# RCMX_Rev_01.net
KiCad netlist of a schematic drawn in EAGLE
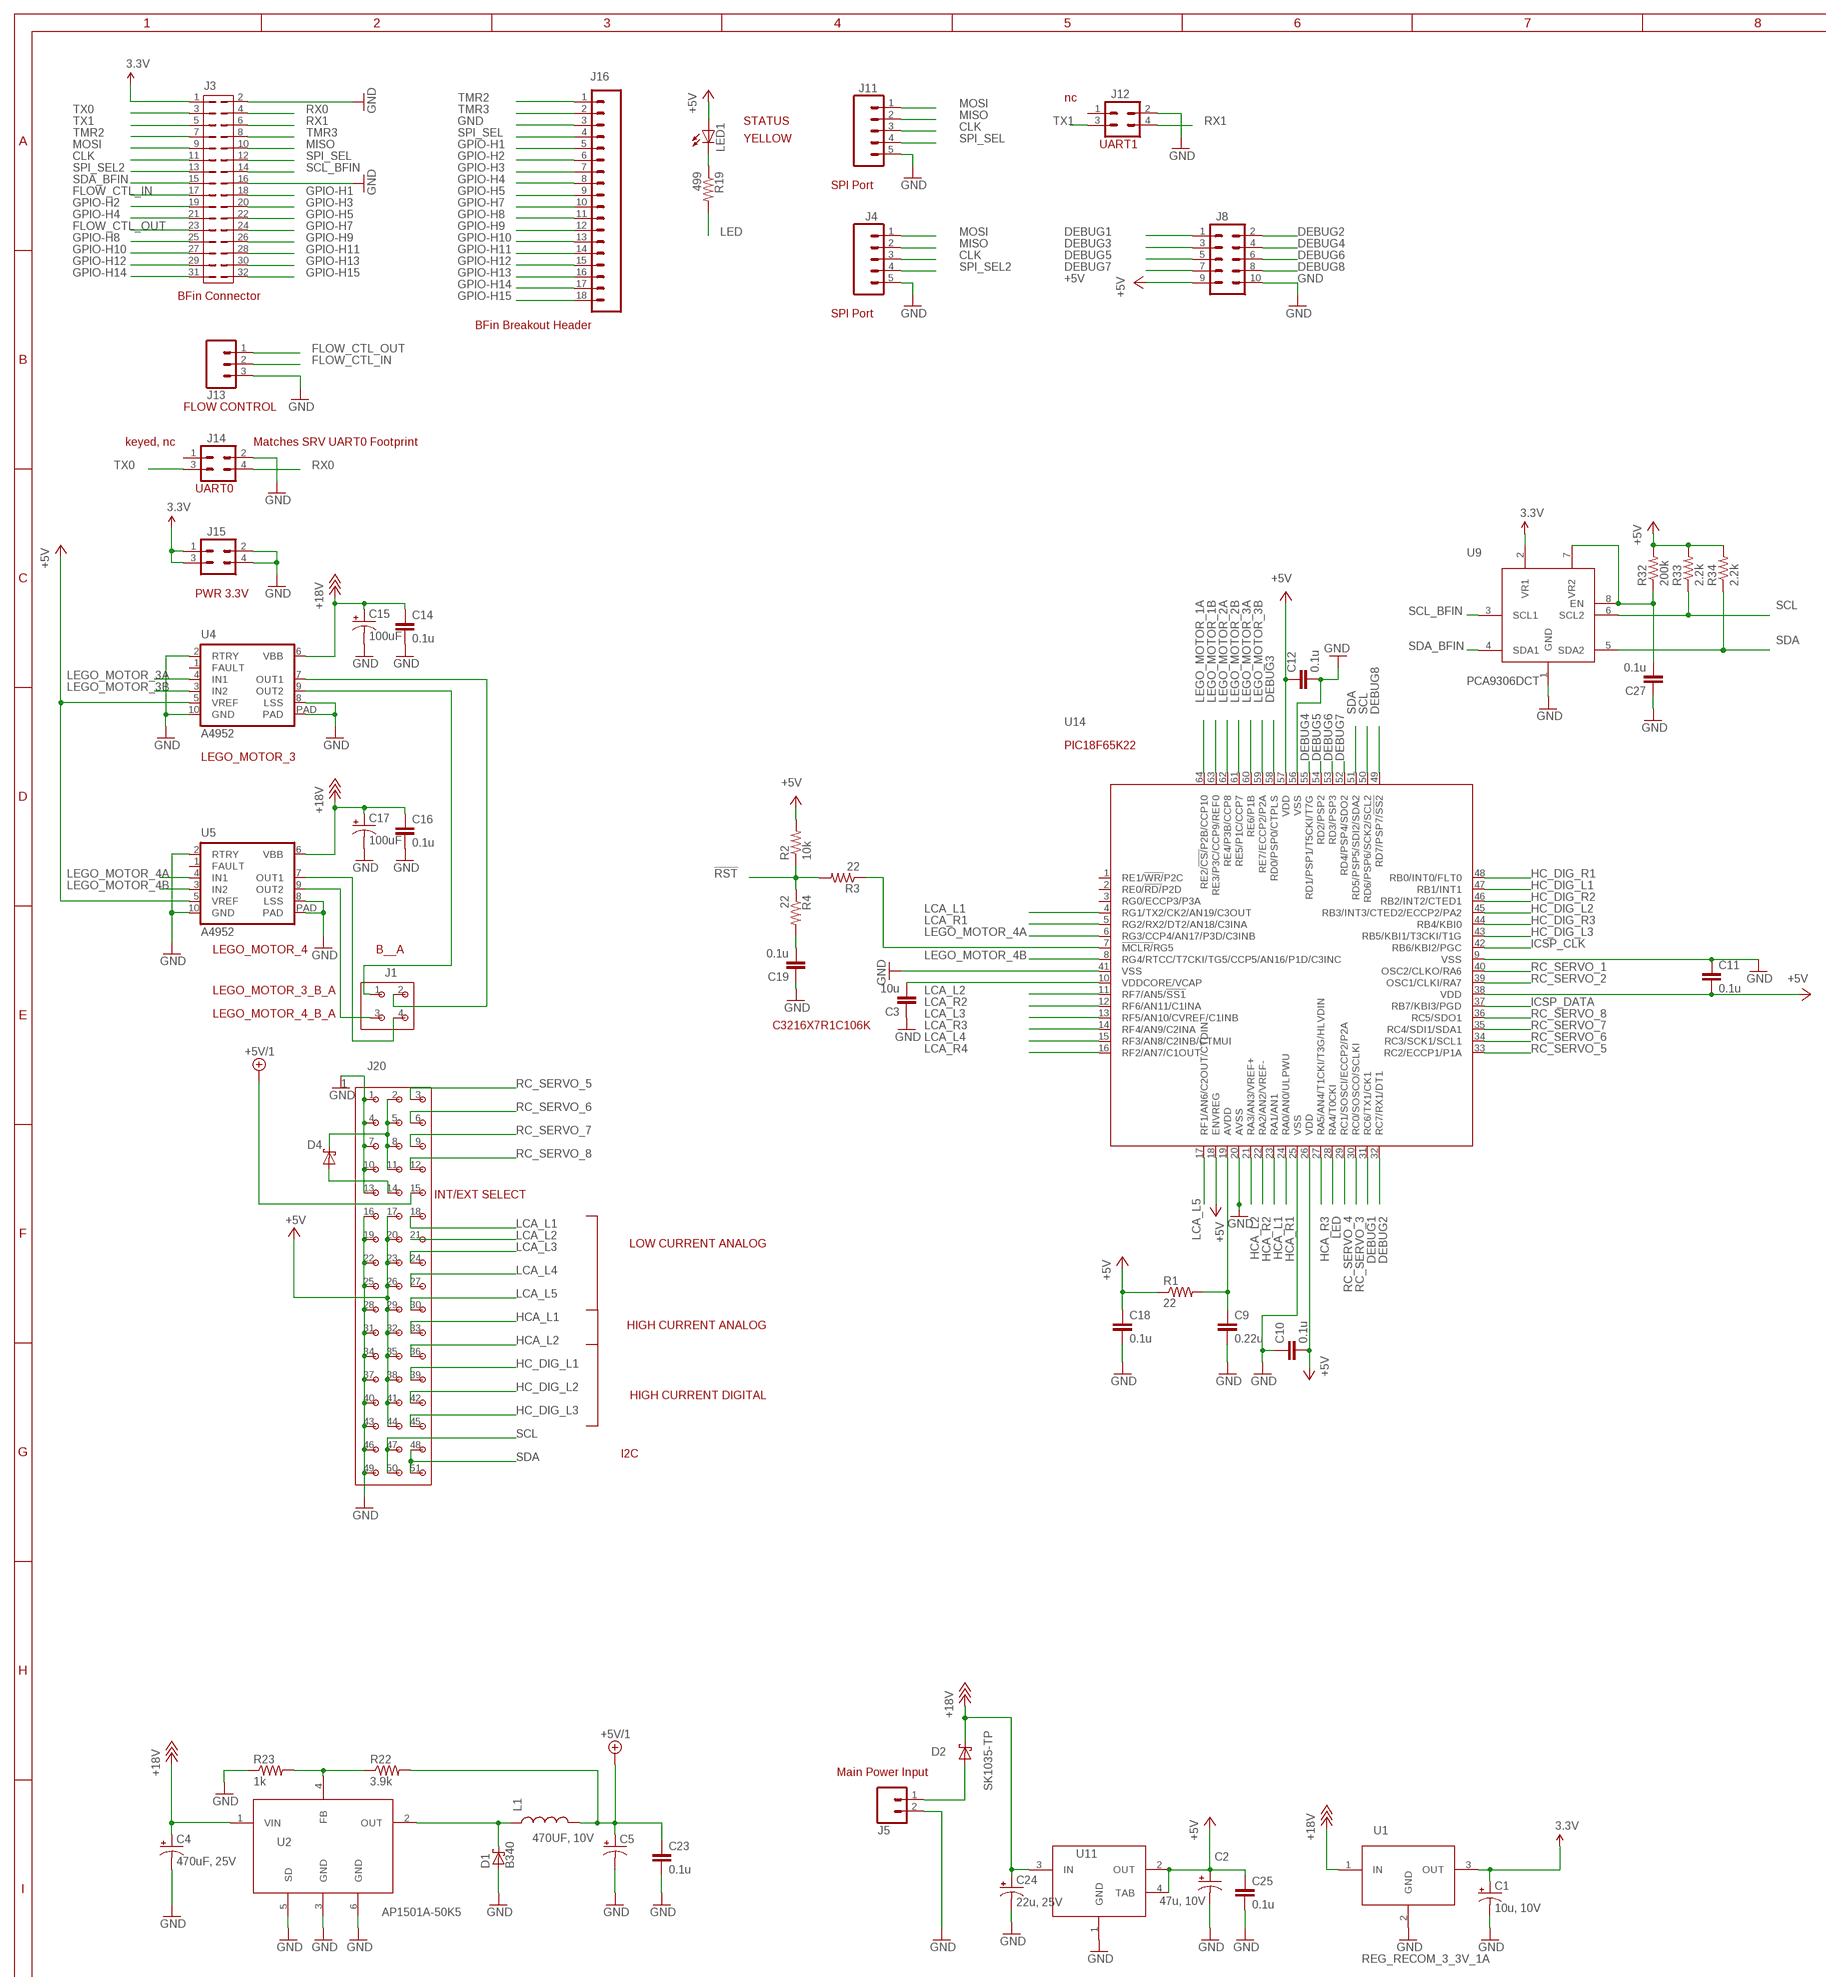
[diagram p0: schematic, sheet 1, part 1 of 2]
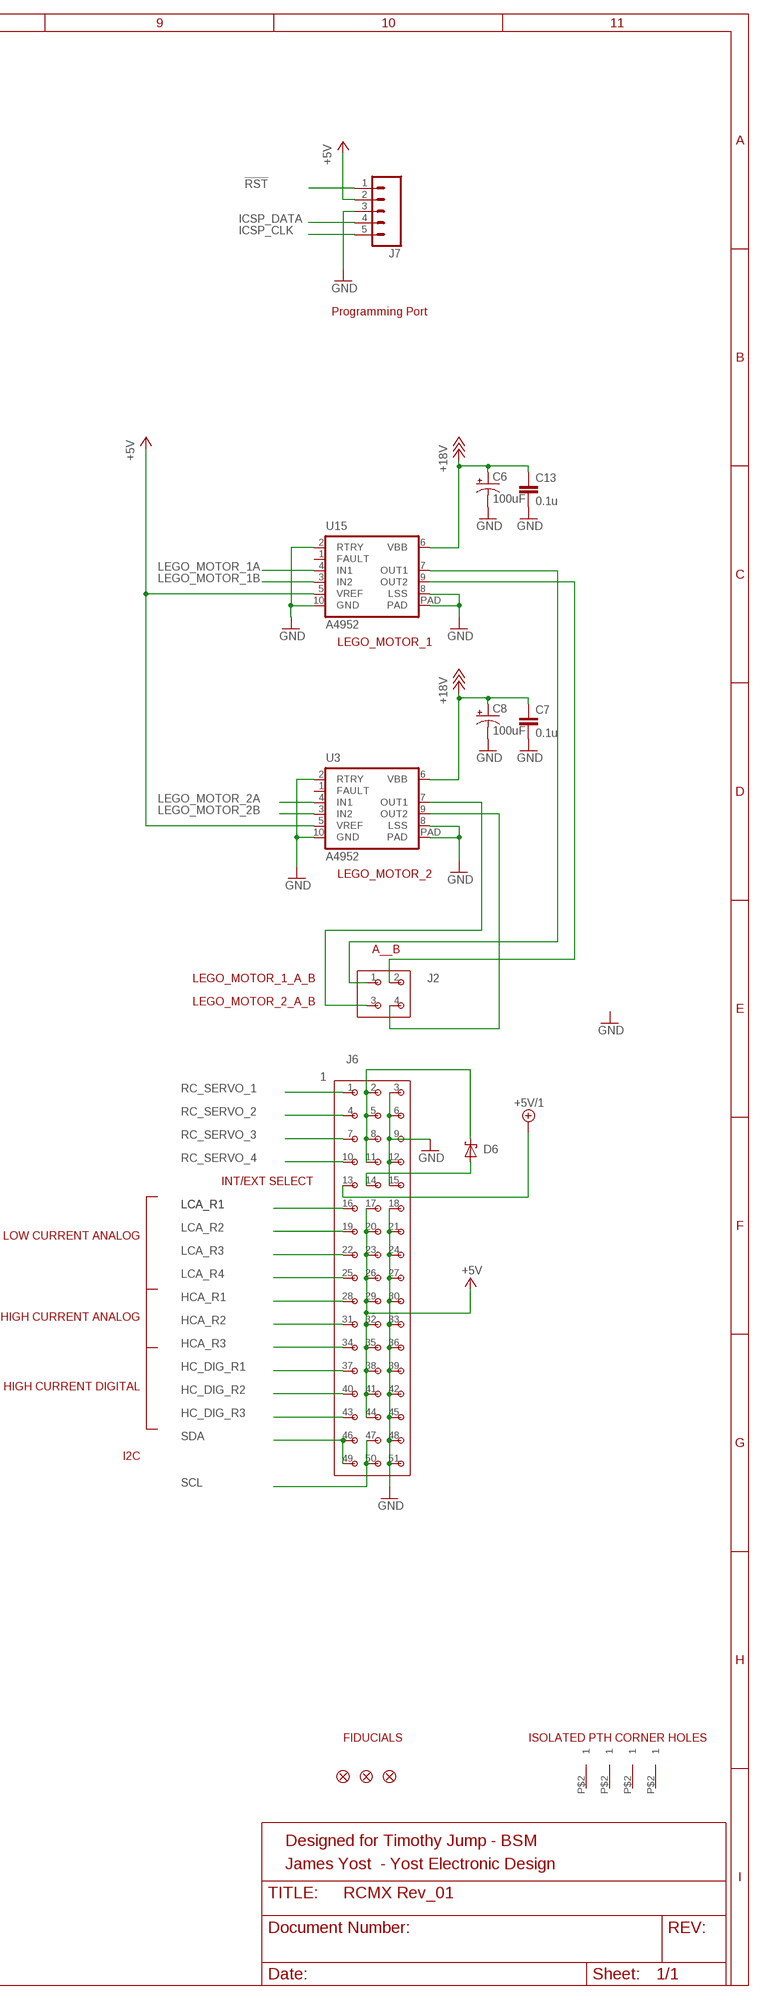
[diagram p1: schematic, sheet 1, part 2 of 2]

(export (version "E")
  (design (tool "Eeschema 10.0.6"))
  (components
    (comp (ref "C1")
      (value "10u, 10V")
      (footprint "eagle-import:EIA3216")
      (libsource (lib "eagle-import") (part "CAP_POL1206"))
    )
    (comp (ref "C2")
      (value "47u, 10V")
      (footprint "eagle-import:CAP1210_POL")
      (libsource (lib "eagle-import") (part "CAP_1210_POL"))
    )
    (comp (ref "C3")
      (value "10u")
      (footprint "eagle-import:1206")
      (libsource (lib "eagle-import") (part "CAP1206"))
    )
    (comp (ref "C4")
      (value "470uF, 25V")
      (footprint "eagle-import:PANASONIC_G")
      (libsource (lib "eagle-import") (part "CAP_POLG"))
    )
    (comp (ref "C5")
      (value "470UF, 10V")
      (footprint "eagle-import:PANASONIC_F")
      (libsource (lib "eagle-import") (part "CAP_ELT_PANASONIC_470UF"))
    )
    (comp (ref "C6")
      (value "100uF")
      (footprint "eagle-import:PANASONIC_D")
      (libsource (lib "eagle-import") (part "CAP_POLD"))
    )
    (comp (ref "C7")
      (value "0.1u")
      (footprint "eagle-import:0805")
      (libsource (lib "eagle-import") (part "CAP0805"))
    )
    (comp (ref "C8")
      (value "100uF")
      (footprint "eagle-import:PANASONIC_D")
      (libsource (lib "eagle-import") (part "CAP_POLD"))
    )
    (comp (ref "C9")
      (value "0.22u")
      (footprint "eagle-import:0805")
      (libsource (lib "eagle-import") (part "CAP0805"))
    )
    (comp (ref "C10")
      (value "0.1u")
      (footprint "eagle-import:0805")
      (libsource (lib "eagle-import") (part "CAP0805"))
    )
    (comp (ref "C11")
      (value "0.1u")
      (footprint "eagle-import:0805")
      (libsource (lib "eagle-import") (part "CAP0805"))
    )
    (comp (ref "C12")
      (value "0.1u")
      (footprint "eagle-import:0805")
      (libsource (lib "eagle-import") (part "CAP0805"))
    )
    (comp (ref "C13")
      (value "0.1u")
      (footprint "eagle-import:0805")
      (libsource (lib "eagle-import") (part "CAP0805"))
    )
    (comp (ref "C14")
      (value "0.1u")
      (footprint "eagle-import:0805")
      (libsource (lib "eagle-import") (part "CAP0805"))
    )
    (comp (ref "C15")
      (value "100uF")
      (footprint "eagle-import:PANASONIC_D")
      (libsource (lib "eagle-import") (part "CAP_POLD"))
    )
    (comp (ref "C16")
      (value "0.1u")
      (footprint "eagle-import:0805")
      (libsource (lib "eagle-import") (part "CAP0805"))
    )
    (comp (ref "C17")
      (value "100uF")
      (footprint "eagle-import:PANASONIC_D")
      (libsource (lib "eagle-import") (part "CAP_POLD"))
    )
    (comp (ref "C18")
      (value "0.1u")
      (footprint "eagle-import:0805")
      (libsource (lib "eagle-import") (part "CAP0805"))
    )
    (comp (ref "C19")
      (value "0.1u")
      (footprint "eagle-import:0805")
      (libsource (lib "eagle-import") (part "CAP0805"))
    )
    (comp (ref "C23")
      (value "0.1u")
      (footprint "eagle-import:0805")
      (libsource (lib "eagle-import") (part "CAP0805"))
    )
    (comp (ref "C24")
      (value "22u, 25V")
      (footprint "eagle-import:CAP1210_POL")
      (libsource (lib "eagle-import") (part "CAP_1210_POL"))
    )
    (comp (ref "C25")
      (value "0.1u")
      (footprint "eagle-import:0805")
      (libsource (lib "eagle-import") (part "CAP0805"))
    )
    (comp (ref "C27")
      (value "0.1u")
      (footprint "eagle-import:0805")
      (libsource (lib "eagle-import") (part "CAP0805"))
    )
    (comp (ref "D1")
      (value "B340")
      (footprint "eagle-import:SMA_DO214AC")
      (libsource (lib "eagle-import") (part "B340"))
    )
    (comp (ref "D2")
      (value "SK1035-TP")
      (footprint "eagle-import:DO214AB")
      (libsource (lib "eagle-import") (part "SK1035-TP"))
    )
    (comp (ref "D4")
      (value "SK1035-TP")
      (footprint "eagle-import:DO214AB")
      (libsource (lib "eagle-import") (part "SK1035-TP"))
    )
    (comp (ref "D6")
      (value "SK1035-TP")
      (footprint "eagle-import:DO214AB")
      (libsource (lib "eagle-import") (part "SK1035-TP"))
    )
    (comp (ref "J1")
      (value "CON_2X2_0_100")
      (footprint "eagle-import:CON_2X2_0_100")
      (libsource (lib "eagle-import") (part "CON_2X2_0_100"))
    )
    (comp (ref "J2")
      (value "CON_2X2_0_100")
      (footprint "eagle-import:CON_2X2_0_100")
      (libsource (lib "eagle-import") (part "CON_2X2_0_100"))
    )
    (comp (ref "J3")
      (value "CON_2X16_0_100")
      (footprint "eagle-import:CON_2X16_0_100")
      (libsource (lib "eagle-import") (part "CON_2X16_0_100"))
    )
    (comp (ref "J4")
      (value "M05PTH")
      (footprint "eagle-import:1X05")
      (libsource (lib "eagle-import") (part "M05PTH"))
    )
    (comp (ref "J5")
      (value "M02NG")
      (footprint "eagle-import:1X02")
      (libsource (lib "eagle-import") (part "M02NG"))
    )
    (comp (ref "J6")
      (value "CON_3X17_0_100")
      (footprint "eagle-import:CON_3X17_0_100")
      (libsource (lib "eagle-import") (part "CON_3X17_0_100"))
    )
    (comp (ref "J7")
      (value "M05PTH")
      (footprint "eagle-import:1X05")
      (libsource (lib "eagle-import") (part "SparkFun-Connectors_M05PTH"))
    )
    (comp (ref "J8")
      (value "M05X2PTH")
      (footprint "eagle-import:AVR_ICSP")
      (libsource (lib "eagle-import") (part "M05X2PTH"))
    )
    (comp (ref "J11")
      (value "M05PTH")
      (footprint "eagle-import:1X05")
      (libsource (lib "eagle-import") (part "M05PTH"))
    )
    (comp (ref "J12")
      (value "CON2X2")
      (footprint "eagle-import:CON2X2")
      (libsource (lib "eagle-import") (part "CON2X2"))
    )
    (comp (ref "J13")
      (value "M03PTH")
      (footprint "eagle-import:1X03")
      (libsource (lib "eagle-import") (part "M03PTH"))
    )
    (comp (ref "J14")
      (value "CON2X2")
      (footprint "eagle-import:CON2X2")
      (libsource (lib "eagle-import") (part "CON2X2"))
    )
    (comp (ref "J15")
      (value "CON2X2")
      (footprint "eagle-import:CON2X2")
      (libsource (lib "eagle-import") (part "CON2X2"))
    )
    (comp (ref "J16")
      (value "CON1X18")
      (footprint "eagle-import:CON1X18")
      (libsource (lib "eagle-import") (part "CON1X18"))
    )
    (comp (ref "J20")
      (value "CON_3X17_0_100")
      (footprint "eagle-import:CON_3X17_0_100")
      (libsource (lib "eagle-import") (part "CON_3X17_0_100"))
    )
    (comp (ref "L1")
      (value "IND_47UH_COILTRONICS_2_95A")
      (footprint "eagle-import:IND_PADS_SMT")
      (libsource (lib "eagle-import") (part "IND_47UH_COILTRONICS_2_95A"))
    )
    (comp (ref "LED1")
      (value "LEDCHIP-LED0805")
      (footprint "eagle-import:CHIP-LED0805")
      (libsource (lib "eagle-import") (part "LEDCHIP-LED0805"))
    )
    (comp (ref "R1")
      (value "22")
      (footprint "eagle-import:0805")
      (libsource (lib "eagle-import") (part "RESISTOR"))
    )
    (comp (ref "R2")
      (value "10k")
      (footprint "eagle-import:0805")
      (libsource (lib "eagle-import") (part "RESISTOR"))
    )
    (comp (ref "R3")
      (value "22")
      (footprint "eagle-import:0805")
      (libsource (lib "eagle-import") (part "RESISTOR"))
    )
    (comp (ref "R4")
      (value "22")
      (footprint "eagle-import:0805")
      (libsource (lib "eagle-import") (part "RESISTOR"))
    )
    (comp (ref "R19")
      (value "499")
      (footprint "eagle-import:0805")
      (libsource (lib "eagle-import") (part "RESISTOR"))
    )
    (comp (ref "R22")
      (value "3.9k")
      (footprint "eagle-import:0805")
      (libsource (lib "eagle-import") (part "RESISTOR"))
    )
    (comp (ref "R23")
      (value "1k")
      (footprint "eagle-import:0805")
      (libsource (lib "eagle-import") (part "RESISTOR"))
    )
    (comp (ref "R32")
      (value "200k")
      (footprint "eagle-import:0805")
      (libsource (lib "eagle-import") (part "RESISTOR"))
    )
    (comp (ref "R33")
      (value "2.2k")
      (footprint "eagle-import:0805")
      (libsource (lib "eagle-import") (part "RESISTOR"))
    )
    (comp (ref "R34")
      (value "2.2k")
      (footprint "eagle-import:0805")
      (libsource (lib "eagle-import") (part "RESISTOR"))
    )
    (comp (ref "U$1")
      (value "GNDPAD")
      (footprint "eagle-import:GNDPAD")
      (libsource (lib "eagle-import") (part "GNDPAD"))
    )
    (comp (ref "U$2")
      (value "GNDPAD")
      (footprint "eagle-import:GNDPAD")
      (libsource (lib "eagle-import") (part "GNDPAD"))
    )
    (comp (ref "U$3")
      (value "FIDUCIAL1X2.5")
      (footprint "eagle-import:FIDUCIAL-1X2.5")
      (libsource (lib "eagle-import") (part "FIDUCIAL1X2.5"))
    )
    (comp (ref "U$4")
      (value "FIDUCIAL1X2.5")
      (footprint "eagle-import:FIDUCIAL-1X2.5")
      (libsource (lib "eagle-import") (part "FIDUCIAL1X2.5"))
    )
    (comp (ref "U$5")
      (value "FIDUCIAL1X2.5")
      (footprint "eagle-import:FIDUCIAL-1X2.5")
      (libsource (lib "eagle-import") (part "FIDUCIAL1X2.5"))
    )
    (comp (ref "U$7")
      (value "GNDPAD")
      (footprint "eagle-import:GNDPAD")
      (libsource (lib "eagle-import") (part "GNDPAD"))
    )
    (comp (ref "U$8")
      (value "GNDPAD")
      (footprint "eagle-import:GNDPAD")
      (libsource (lib "eagle-import") (part "GNDPAD"))
    )
    (comp (ref "U1")
      (value "REG_RECOM_3_3V_1A")
      (footprint "eagle-import:REG_RECOM_3_3V_1A")
      (libsource (lib "eagle-import") (part "REG_RECOM_3_3V_1A"))
    )
    (comp (ref "U2")
      (value "AP1501A-50K5")
      (footprint "eagle-import:TO263-5")
      (libsource (lib "eagle-import") (part "AP1501A-50K5"))
    )
    (comp (ref "U3")
      (value "A4952")
      (footprint "eagle-import:MSOP10_W_THERMAL_PAD")
      (libsource (lib "eagle-import") (part "A4952"))
    )
    (comp (ref "U4")
      (value "A4952")
      (footprint "eagle-import:MSOP10_W_THERMAL_PAD")
      (libsource (lib "eagle-import") (part "A4952"))
    )
    (comp (ref "U5")
      (value "A4952")
      (footprint "eagle-import:MSOP10_W_THERMAL_PAD")
      (libsource (lib "eagle-import") (part "A4952"))
    )
    (comp (ref "U9")
      (value "PCA9306DCT")
      (footprint "eagle-import:TEST08")
      (libsource (lib "eagle-import") (part "PCA9306DCT"))
    )
    (comp (ref "U11")
      (value "TLV1117-5")
      (footprint "eagle-import:SOT223")
      (libsource (lib "eagle-import") (part "TLV1117-5"))
    )
    (comp (ref "U14")
      (value "MICRO_C_PIC18F65K22")
      (footprint "eagle-import:64PIN_TQFP_10X10X1MM")
      (libsource (lib "eagle-import") (part "MICRO_C_PIC18F65K22"))
    )
    (comp (ref "U15")
      (value "A4952")
      (footprint "eagle-import:MSOP10_W_THERMAL_PAD")
      (libsource (lib "eagle-import") (part "A4952"))
    )
  )
  (nets
    (net (code "1") (name "+5V") (class "Default")
      (node (ref "C10") (pin "2") (pinfunction "2_2") (pintype "passive"))
      (node (ref "C11") (pin "2") (pinfunction "2_2") (pintype "passive"))
      (node (ref "C12") (pin "1") (pinfunction "1_1") (pintype "passive"))
      (node (ref "C18") (pin "1") (pinfunction "1_1") (pintype "passive"))
      (node (ref "C2") (pin "1") (pinfunction "+_1") (pintype "passive"))
      (node (ref "C25") (pin "1") (pinfunction "1_1") (pintype "passive"))
      (node (ref "J20") (pin "17") (pinfunction "17_17") (pintype "passive"))
      (node (ref "J20") (pin "20") (pinfunction "20_20") (pintype "passive"))
      (node (ref "J20") (pin "23") (pinfunction "23_23") (pintype "passive"))
      (node (ref "J20") (pin "26") (pinfunction "26_26") (pintype "passive"))
      (node (ref "J20") (pin "29") (pinfunction "29_29") (pintype "passive"))
      (node (ref "J20") (pin "32") (pinfunction "32_32") (pintype "passive"))
      (node (ref "J20") (pin "35") (pinfunction "35_35") (pintype "passive"))
      (node (ref "J20") (pin "38") (pinfunction "38_38") (pintype "passive"))
      (node (ref "J20") (pin "41") (pinfunction "41_41") (pintype "passive"))
      (node (ref "J20") (pin "44") (pinfunction "44_44") (pintype "passive"))
      (node (ref "J6") (pin "17") (pinfunction "17_17") (pintype "passive"))
      (node (ref "J6") (pin "20") (pinfunction "20_20") (pintype "passive"))
      (node (ref "J6") (pin "23") (pinfunction "23_23") (pintype "passive"))
      (node (ref "J6") (pin "26") (pinfunction "26_26") (pintype "passive"))
      (node (ref "J6") (pin "29") (pinfunction "29_29") (pintype "passive"))
      (node (ref "J6") (pin "32") (pinfunction "32_32") (pintype "passive"))
      (node (ref "J6") (pin "35") (pinfunction "35_35") (pintype "passive"))
      (node (ref "J6") (pin "38") (pinfunction "38_38") (pintype "passive"))
      (node (ref "J6") (pin "41") (pinfunction "41_41") (pintype "passive"))
      (node (ref "J6") (pin "44") (pinfunction "44_44") (pintype "passive"))
      (node (ref "J7") (pin "2") (pinfunction "2_2") (pintype "passive"))
      (node (ref "J8") (pin "9") (pinfunction "9_9") (pintype "passive"))
      (node (ref "LED1") (pin "A") (pinfunction "A_A") (pintype "passive"))
      (node (ref "R1") (pin "1") (pinfunction "1_1") (pintype "passive"))
      (node (ref "R2") (pin "2") (pinfunction "2_2") (pintype "passive"))
      (node (ref "R32") (pin "2") (pinfunction "2_2") (pintype "passive"))
      (node (ref "R33") (pin "2") (pinfunction "2_2") (pintype "passive"))
      (node (ref "R34") (pin "2") (pinfunction "2_2") (pintype "passive"))
      (node (ref "U11") (pin "2") (pinfunction "OUT_2") (pintype "bidirectional"))
      (node (ref "U11") (pin "4") (pinfunction "TAB_4") (pintype "bidirectional"))
      (node (ref "U14") (pin "18") (pinfunction "ENVREG_18") (pintype "input"))
      (node (ref "U14") (pin "26") (pinfunction "VDD_26") (pintype "power_in"))
      (node (ref "U14") (pin "38") (pinfunction "VDD_38") (pintype "power_in"))
      (node (ref "U14") (pin "57") (pinfunction "VDD_57") (pintype "power_in"))
      (node (ref "U15") (pin "5") (pinfunction "VREF_5") (pintype "passive"))
      (node (ref "U3") (pin "5") (pinfunction "VREF_5") (pintype "passive"))
      (node (ref "U4") (pin "5") (pinfunction "VREF_5") (pintype "passive"))
      (node (ref "U5") (pin "5") (pinfunction "VREF_5") (pintype "passive"))
    )
    (net (code "2") (name "+5V{slash}1") (class "Default")
      (node (ref "C23") (pin "1") (pinfunction "1_1") (pintype "passive"))
      (node (ref "C5") (pin "+") (pinfunction "+_+") (pintype "passive"))
      (node (ref "J20") (pin "15") (pinfunction "15_15") (pintype "passive"))
      (node (ref "J6") (pin "13") (pinfunction "13_13") (pintype "passive"))
      (node (ref "L1") (pin "2") (pinfunction "2_2") (pintype "passive"))
      (node (ref "R22") (pin "2") (pinfunction "2_2") (pintype "passive"))
    )
    (net (code "3") (name "+18V") (class "Default")
      (node (ref "C13") (pin "1") (pinfunction "1_1") (pintype "passive"))
      (node (ref "C14") (pin "1") (pinfunction "1_1") (pintype "passive"))
      (node (ref "C15") (pin "+") (pinfunction "+_+") (pintype "passive"))
      (node (ref "C16") (pin "1") (pinfunction "1_1") (pintype "passive"))
      (node (ref "C17") (pin "+") (pinfunction "+_+") (pintype "passive"))
      (node (ref "C24") (pin "1") (pinfunction "+_1") (pintype "passive"))
      (node (ref "C4") (pin "+") (pinfunction "+_+") (pintype "passive"))
      (node (ref "C6") (pin "+") (pinfunction "+_+") (pintype "passive"))
      (node (ref "C7") (pin "1") (pinfunction "1_1") (pintype "passive"))
      (node (ref "C8") (pin "+") (pinfunction "+_+") (pintype "passive"))
      (node (ref "D2") (pin "1") (pinfunction "C_1") (pintype "passive"))
      (node (ref "U1") (pin "1") (pinfunction "IN_1") (pintype "bidirectional"))
      (node (ref "U11") (pin "3") (pinfunction "IN_3") (pintype "bidirectional"))
      (node (ref "U15") (pin "6") (pinfunction "VBB_6") (pintype "input"))
      (node (ref "U2") (pin "1") (pinfunction "VIN_1") (pintype "bidirectional"))
      (node (ref "U3") (pin "6") (pinfunction "VBB_6") (pintype "input"))
      (node (ref "U4") (pin "6") (pinfunction "VBB_6") (pintype "input"))
      (node (ref "U5") (pin "6") (pinfunction "VBB_6") (pintype "input"))
    )
    (net (code "4") (name "/CLK") (class "Default")
      (node (ref "J11") (pin "3") (pinfunction "3_3") (pintype "passive"))
      (node (ref "J3") (pin "11") (pinfunction "11_11") (pintype "passive"))
      (node (ref "J4") (pin "3") (pinfunction "3_3") (pintype "passive"))
    )
    (net (code "5") (name "/DEBUG1") (class "Default")
      (node (ref "J8") (pin "1") (pinfunction "1_1") (pintype "passive"))
      (node (ref "U14") (pin "31") (pinfunction "RC6/TX1/CK1_31") (pintype "bidirectional"))
    )
    (net (code "6") (name "/DEBUG2") (class "Default")
      (node (ref "J8") (pin "2") (pinfunction "2_2") (pintype "passive"))
      (node (ref "U14") (pin "32") (pinfunction "RC7/RX1/DT1_32") (pintype "bidirectional"))
    )
    (net (code "7") (name "/DEBUG3") (class "Default")
      (node (ref "J8") (pin "3") (pinfunction "3_3") (pintype "passive"))
      (node (ref "U14") (pin "58") (pinfunction "RD0/PSP0/CTPLS_58") (pintype "bidirectional"))
    )
    (net (code "8") (name "/DEBUG4") (class "Default")
      (node (ref "J8") (pin "4") (pinfunction "4_4") (pintype "passive"))
      (node (ref "U14") (pin "55") (pinfunction "RD1/PSP1/T5CKI/T7G_55") (pintype "bidirectional"))
    )
    (net (code "9") (name "/DEBUG5") (class "Default")
      (node (ref "J8") (pin "5") (pinfunction "5_5") (pintype "passive"))
      (node (ref "U14") (pin "54") (pinfunction "RD2/PSP2_54") (pintype "bidirectional"))
    )
    (net (code "10") (name "/DEBUG6") (class "Default")
      (node (ref "J8") (pin "6") (pinfunction "6_6") (pintype "passive"))
      (node (ref "U14") (pin "53") (pinfunction "RD3/PSP3_53") (pintype "bidirectional"))
    )
    (net (code "11") (name "/DEBUG7") (class "Default")
      (node (ref "J8") (pin "7") (pinfunction "7_7") (pintype "passive"))
      (node (ref "U14") (pin "52") (pinfunction "RD4/PSP4/SDO2_52") (pintype "bidirectional"))
    )
    (net (code "12") (name "/DEBUG8") (class "Default")
      (node (ref "J8") (pin "8") (pinfunction "8_8") (pintype "passive"))
      (node (ref "U14") (pin "49") (pinfunction "RD7/PSP7/~{SS2}_49") (pintype "bidirectional"))
    )
    (net (code "13") (name "/FLOW_CTL_IN") (class "Default")
      (node (ref "J13") (pin "2") (pinfunction "2_2") (pintype "passive"))
      (node (ref "J3") (pin "17") (pinfunction "17_17") (pintype "passive"))
    )
    (net (code "14") (name "/FLOW_CTL_OUT") (class "Default")
      (node (ref "J13") (pin "1") (pinfunction "1_1") (pintype "passive"))
      (node (ref "J3") (pin "23") (pinfunction "23_23") (pintype "passive"))
    )
    (net (code "15") (name "/GPIO-H1") (class "Default")
      (node (ref "J16") (pin "5") (pinfunction "5_5") (pintype "passive"))
      (node (ref "J3") (pin "18") (pinfunction "18_18") (pintype "passive"))
    )
    (net (code "16") (name "/GPIO-H2") (class "Default")
      (node (ref "J16") (pin "6") (pinfunction "6_6") (pintype "passive"))
      (node (ref "J3") (pin "19") (pinfunction "19_19") (pintype "passive"))
    )
    (net (code "17") (name "/GPIO-H3") (class "Default")
      (node (ref "J16") (pin "7") (pinfunction "7_7") (pintype "passive"))
      (node (ref "J3") (pin "20") (pinfunction "20_20") (pintype "passive"))
    )
    (net (code "18") (name "/GPIO-H4") (class "Default")
      (node (ref "J16") (pin "8") (pinfunction "8_8") (pintype "passive"))
      (node (ref "J3") (pin "21") (pinfunction "21_21") (pintype "passive"))
    )
    (net (code "19") (name "/GPIO-H5") (class "Default")
      (node (ref "J16") (pin "9") (pinfunction "9_9") (pintype "passive"))
      (node (ref "J3") (pin "22") (pinfunction "22_22") (pintype "passive"))
    )
    (net (code "20") (name "/GPIO-H7") (class "Default")
      (node (ref "J16") (pin "10") (pinfunction "10_10") (pintype "passive"))
      (node (ref "J3") (pin "24") (pinfunction "24_24") (pintype "passive"))
    )
    (net (code "21") (name "/GPIO-H8") (class "Default")
      (node (ref "J16") (pin "11") (pinfunction "11_11") (pintype "passive"))
      (node (ref "J3") (pin "25") (pinfunction "25_25") (pintype "passive"))
    )
    (net (code "22") (name "/GPIO-H9") (class "Default")
      (node (ref "J16") (pin "12") (pinfunction "12_12") (pintype "passive"))
      (node (ref "J3") (pin "26") (pinfunction "26_26") (pintype "passive"))
    )
    (net (code "23") (name "/GPIO-H10") (class "Default")
      (node (ref "J16") (pin "13") (pinfunction "13_13") (pintype "passive"))
      (node (ref "J3") (pin "27") (pinfunction "27_27") (pintype "passive"))
    )
    (net (code "24") (name "/GPIO-H11") (class "Default")
      (node (ref "J16") (pin "14") (pinfunction "14_14") (pintype "passive"))
      (node (ref "J3") (pin "28") (pinfunction "28_28") (pintype "passive"))
    )
    (net (code "25") (name "/GPIO-H12") (class "Default")
      (node (ref "J16") (pin "15") (pinfunction "15_15") (pintype "passive"))
      (node (ref "J3") (pin "29") (pinfunction "29_29") (pintype "passive"))
    )
    (net (code "26") (name "/GPIO-H13") (class "Default")
      (node (ref "J16") (pin "16") (pinfunction "16_16") (pintype "passive"))
      (node (ref "J3") (pin "30") (pinfunction "30_30") (pintype "passive"))
    )
    (net (code "27") (name "/GPIO-H14") (class "Default")
      (node (ref "J16") (pin "17") (pinfunction "17_17") (pintype "passive"))
      (node (ref "J3") (pin "31") (pinfunction "31_31") (pintype "passive"))
    )
    (net (code "28") (name "/GPIO-H15") (class "Default")
      (node (ref "J16") (pin "18") (pinfunction "18_18") (pintype "passive"))
      (node (ref "J3") (pin "32") (pinfunction "32_32") (pintype "passive"))
    )
    (net (code "29") (name "/HCA_L1") (class "Default")
      (node (ref "J20") (pin "33") (pinfunction "33_33") (pintype "passive"))
      (node (ref "U14") (pin "23") (pinfunction "RA1/AN1_23") (pintype "bidirectional"))
    )
    (net (code "30") (name "/HCA_L2") (class "Default")
      (node (ref "J20") (pin "36") (pinfunction "36_36") (pintype "passive"))
      (node (ref "U14") (pin "21") (pinfunction "RA3/AN3/VREF+_21") (pintype "bidirectional"))
    )
    (net (code "31") (name "/HCA_R1") (class "Default")
      (node (ref "J6") (pin "28") (pinfunction "28_28") (pintype "passive"))
      (node (ref "U14") (pin "24") (pinfunction "RA0/AN0/ULPWU_24") (pintype "bidirectional"))
    )
    (net (code "32") (name "/HCA_R2") (class "Default")
      (node (ref "J6") (pin "31") (pinfunction "31_31") (pintype "passive"))
      (node (ref "U14") (pin "22") (pinfunction "RA2/AN2/VREF-_22") (pintype "bidirectional"))
    )
    (net (code "33") (name "/HCA_R3") (class "Default")
      (node (ref "J6") (pin "34") (pinfunction "34_34") (pintype "passive"))
      (node (ref "U14") (pin "27") (pinfunction "RA5/AN4/T1CKI/T3G/HLVDIN_27") (pintype "bidirectional"))
    )
    (net (code "34") (name "/HC_DIG_L1") (class "Default")
      (node (ref "J20") (pin "39") (pinfunction "39_39") (pintype "passive"))
      (node (ref "U14") (pin "47") (pinfunction "RB1/INT1_47") (pintype "bidirectional"))
    )
    (net (code "35") (name "/HC_DIG_L2") (class "Default")
      (node (ref "J20") (pin "42") (pinfunction "42_42") (pintype "passive"))
      (node (ref "U14") (pin "45") (pinfunction "RB3/INT3/CTED2/ECCP2/PA2_45") (pintype "bidirectional"))
    )
    (net (code "36") (name "/HC_DIG_L3") (class "Default")
      (node (ref "J20") (pin "45") (pinfunction "45_45") (pintype "passive"))
      (node (ref "U14") (pin "43") (pinfunction "RB5/KBI1/T3CKI/T1G_43") (pintype "bidirectional"))
    )
    (net (code "37") (name "/HC_DIG_R1") (class "Default")
      (node (ref "J6") (pin "37") (pinfunction "37_37") (pintype "passive"))
      (node (ref "U14") (pin "48") (pinfunction "RB0/INT0/FLT0_48") (pintype "bidirectional"))
    )
    (net (code "38") (name "/HC_DIG_R2") (class "Default")
      (node (ref "J6") (pin "40") (pinfunction "40_40") (pintype "passive"))
      (node (ref "U14") (pin "46") (pinfunction "RB2/INT2/CTED1_46") (pintype "bidirectional"))
    )
    (net (code "39") (name "/HC_DIG_R3") (class "Default")
      (node (ref "J6") (pin "43") (pinfunction "43_43") (pintype "passive"))
      (node (ref "U14") (pin "44") (pinfunction "RB4/KBI0_44") (pintype "bidirectional"))
    )
    (net (code "40") (name "/ICSP_CLK") (class "Default")
      (node (ref "J7") (pin "5") (pinfunction "5_5") (pintype "passive"))
      (node (ref "U14") (pin "42") (pinfunction "RB6/KBI2/PGC_42") (pintype "bidirectional"))
    )
    (net (code "41") (name "/ICSP_DATA") (class "Default")
      (node (ref "J7") (pin "4") (pinfunction "4_4") (pintype "passive"))
      (node (ref "U14") (pin "37") (pinfunction "RB7/KBI3/PGD_37") (pintype "bidirectional"))
    )
    (net (code "42") (name "/LCA_L1") (class "Default")
      (node (ref "J20") (pin "18") (pinfunction "18_18") (pintype "passive"))
      (node (ref "U14") (pin "4") (pinfunction "RG1/TX2/CK2/AN19/C3OUT_4") (pintype "bidirectional"))
    )
    (net (code "43") (name "/LCA_L2") (class "Default")
      (node (ref "J20") (pin "21") (pinfunction "21_21") (pintype "passive"))
      (node (ref "U14") (pin "11") (pinfunction "RF7/AN5/~{SS1}_11") (pintype "bidirectional"))
    )
    (net (code "44") (name "/LCA_L3") (class "Default")
      (node (ref "J20") (pin "24") (pinfunction "24_24") (pintype "passive"))
      (node (ref "U14") (pin "13") (pinfunction "RF5/AN10/CVREF/C1INB_13") (pintype "bidirectional"))
    )
    (net (code "45") (name "/LCA_L4") (class "Default")
      (node (ref "J20") (pin "27") (pinfunction "27_27") (pintype "passive"))
      (node (ref "U14") (pin "15") (pinfunction "RF3/AN8/C2INB/CTMUI_15") (pintype "bidirectional"))
    )
    (net (code "46") (name "/LCA_L5") (class "Default")
      (node (ref "J20") (pin "30") (pinfunction "30_30") (pintype "passive"))
      (node (ref "U14") (pin "17") (pinfunction "RF1/AN6/C2OUT/CTDIN_17") (pintype "bidirectional"))
    )
    (net (code "47") (name "/LCA_R1") (class "Default")
      (node (ref "J6") (pin "16") (pinfunction "16_16") (pintype "passive"))
      (node (ref "U14") (pin "5") (pinfunction "RG2/RX2/DT2/AN18/C3INA_5") (pintype "bidirectional"))
    )
    (net (code "48") (name "/LCA_R2") (class "Default")
      (node (ref "J6") (pin "19") (pinfunction "19_19") (pintype "passive"))
      (node (ref "U14") (pin "12") (pinfunction "RF6/AN11/C1INA_12") (pintype "bidirectional"))
    )
    (net (code "49") (name "/LCA_R3") (class "Default")
      (node (ref "J6") (pin "22") (pinfunction "22_22") (pintype "passive"))
      (node (ref "U14") (pin "14") (pinfunction "RF4/AN9/C2INA_14") (pintype "bidirectional"))
    )
    (net (code "50") (name "/LCA_R4") (class "Default")
      (node (ref "J6") (pin "25") (pinfunction "25_25") (pintype "passive"))
      (node (ref "U14") (pin "16") (pinfunction "RF2/AN7/C1OUT_16") (pintype "bidirectional"))
    )
    (net (code "51") (name "/LED") (class "Default")
      (node (ref "R19") (pin "2") (pinfunction "2_2") (pintype "passive"))
      (node (ref "U14") (pin "28") (pinfunction "RA4/T0CKI_28") (pintype "bidirectional"))
    )
    (net (code "52") (name "/LEGO_MOTOR_1A") (class "Default")
      (node (ref "U14") (pin "64") (pinfunction "RE2/~{CS/}P2B/CCP10_64") (pintype "bidirectional"))
      (node (ref "U15") (pin "4") (pinfunction "IN1_4") (pintype "input"))
    )
    (net (code "53") (name "/LEGO_MOTOR_1B") (class "Default")
      (node (ref "U14") (pin "63") (pinfunction "RE3/P3C/CCP9/REF0_63") (pintype "bidirectional"))
      (node (ref "U15") (pin "3") (pinfunction "IN2_3") (pintype "input"))
    )
    (net (code "54") (name "/LEGO_MOTOR_2A") (class "Default")
      (node (ref "U14") (pin "62") (pinfunction "RE4/P3B/CCP8_62") (pintype "bidirectional"))
      (node (ref "U3") (pin "4") (pinfunction "IN1_4") (pintype "input"))
    )
    (net (code "55") (name "/LEGO_MOTOR_2B") (class "Default")
      (node (ref "U14") (pin "61") (pinfunction "RE5/P1C/CCP7_61") (pintype "bidirectional"))
      (node (ref "U3") (pin "3") (pinfunction "IN2_3") (pintype "input"))
    )
    (net (code "56") (name "/LEGO_MOTOR_3A") (class "Default")
      (node (ref "U14") (pin "60") (pinfunction "RE6/P1B_60") (pintype "bidirectional"))
      (node (ref "U4") (pin "4") (pinfunction "IN1_4") (pintype "input"))
    )
    (net (code "57") (name "/LEGO_MOTOR_3B") (class "Default")
      (node (ref "U14") (pin "59") (pinfunction "RE7/ECCP2/P2A_59") (pintype "bidirectional"))
      (node (ref "U4") (pin "3") (pinfunction "IN2_3") (pintype "input"))
    )
    (net (code "58") (name "/LEGO_MOTOR_4A") (class "Default")
      (node (ref "U14") (pin "6") (pinfunction "RG3/CCP4/AN17/P3D/C3INB_6") (pintype "bidirectional"))
      (node (ref "U5") (pin "4") (pinfunction "IN1_4") (pintype "input"))
    )
    (net (code "59") (name "/LEGO_MOTOR_4B") (class "Default")
      (node (ref "U14") (pin "8") (pinfunction "RG4/RTCC/T7CKI/TG5/CCP5/AN16/P1D/C3INC_8") (pintype "bidirectional"))
      (node (ref "U5") (pin "3") (pinfunction "IN2_3") (pintype "input"))
    )
    (net (code "60") (name "/MISO") (class "Default")
      (node (ref "J11") (pin "2") (pinfunction "2_2") (pintype "passive"))
      (node (ref "J3") (pin "10") (pinfunction "10_10") (pintype "passive"))
      (node (ref "J4") (pin "2") (pinfunction "2_2") (pintype "passive"))
    )
    (net (code "61") (name "/MOSI") (class "Default")
      (node (ref "J11") (pin "1") (pinfunction "1_1") (pintype "passive"))
      (node (ref "J3") (pin "9") (pinfunction "9_9") (pintype "passive"))
      (node (ref "J4") (pin "1") (pinfunction "1_1") (pintype "passive"))
    )
    (net (code "62") (name "/RC_SERVO_1") (class "Default")
      (node (ref "J6") (pin "1") (pinfunction "1_1") (pintype "passive"))
      (node (ref "U14") (pin "40") (pinfunction "OSC2/CLKO/RA6_40") (pintype "output"))
    )
    (net (code "63") (name "/RC_SERVO_2") (class "Default")
      (node (ref "J6") (pin "4") (pinfunction "4_4") (pintype "passive"))
      (node (ref "U14") (pin "39") (pinfunction "OSC1/CLKI/RA7_39") (pintype "input"))
    )
    (net (code "64") (name "/RC_SERVO_3") (class "Default")
      (node (ref "J6") (pin "7") (pinfunction "7_7") (pintype "passive"))
      (node (ref "U14") (pin "30") (pinfunction "RC0/SOSCO/SCLKI_30") (pintype "bidirectional"))
    )
    (net (code "65") (name "/RC_SERVO_4") (class "Default")
      (node (ref "J6") (pin "10") (pinfunction "10_10") (pintype "passive"))
      (node (ref "U14") (pin "29") (pinfunction "RC1/SOSCI/ECCP2/P2A_29") (pintype "bidirectional"))
    )
    (net (code "66") (name "/RC_SERVO_5") (class "Default")
      (node (ref "J20") (pin "3") (pinfunction "3_3") (pintype "passive"))
      (node (ref "U14") (pin "33") (pinfunction "RC2/ECCP1/P1A_33") (pintype "bidirectional"))
    )
    (net (code "67") (name "/RC_SERVO_6") (class "Default")
      (node (ref "J20") (pin "6") (pinfunction "6_6") (pintype "passive"))
      (node (ref "U14") (pin "34") (pinfunction "RC3/SCK1/SCL1_34") (pintype "bidirectional"))
    )
    (net (code "68") (name "/RC_SERVO_7") (class "Default")
      (node (ref "J20") (pin "9") (pinfunction "9_9") (pintype "passive"))
      (node (ref "U14") (pin "35") (pinfunction "RC4/SDI1/SDA1_35") (pintype "bidirectional"))
    )
    (net (code "69") (name "/RC_SERVO_8") (class "Default")
      (node (ref "J20") (pin "12") (pinfunction "12_12") (pintype "passive"))
      (node (ref "U14") (pin "36") (pinfunction "RC5/SDO1_36") (pintype "bidirectional"))
    )
    (net (code "70") (name "/RX0") (class "Default")
      (node (ref "J14") (pin "4") (pinfunction "4_4") (pintype "passive"))
      (node (ref "J3") (pin "4") (pinfunction "4_4") (pintype "passive"))
    )
    (net (code "71") (name "/RX1") (class "Default")
      (node (ref "J12") (pin "4") (pinfunction "4_4") (pintype "passive"))
      (node (ref "J3") (pin "6") (pinfunction "6_6") (pintype "passive"))
    )
    (net (code "72") (name "/SCL") (class "Default")
      (node (ref "J20") (pin "47") (pinfunction "47_47") (pintype "passive"))
      (node (ref "J20") (pin "50") (pinfunction "50_50") (pintype "passive"))
      (node (ref "J6") (pin "47") (pinfunction "47_47") (pintype "passive"))
      (node (ref "J6") (pin "50") (pinfunction "50_50") (pintype "passive"))
      (node (ref "R33") (pin "1") (pinfunction "1_1") (pintype "passive"))
      (node (ref "U14") (pin "50") (pinfunction "RD6/PSP6/SCK2/SCL2_50") (pintype "bidirectional"))
      (node (ref "U9") (pin "6") (pinfunction "SCL2_6") (pintype "bidirectional"))
    )
    (net (code "73") (name "/SCL_BFIN") (class "Default")
      (node (ref "J3") (pin "14") (pinfunction "14_14") (pintype "passive"))
      (node (ref "U9") (pin "3") (pinfunction "SCL1_3") (pintype "bidirectional"))
    )
    (net (code "74") (name "/SDA") (class "Default")
      (node (ref "J20") (pin "48") (pinfunction "48_48") (pintype "passive"))
      (node (ref "J20") (pin "51") (pinfunction "51_51") (pintype "passive"))
      (node (ref "J6") (pin "46") (pinfunction "46_46") (pintype "passive"))
      (node (ref "J6") (pin "49") (pinfunction "49_49") (pintype "passive"))
      (node (ref "R34") (pin "1") (pinfunction "1_1") (pintype "passive"))
      (node (ref "U14") (pin "51") (pinfunction "RD5/PSP5/SDI2/SDA2_51") (pintype "bidirectional"))
      (node (ref "U9") (pin "5") (pinfunction "SDA2_5") (pintype "bidirectional"))
    )
    (net (code "75") (name "/SDA_BFIN") (class "Default")
      (node (ref "J3") (pin "15") (pinfunction "15_15") (pintype "passive"))
      (node (ref "U9") (pin "4") (pinfunction "SDA1_4") (pintype "bidirectional"))
    )
    (net (code "76") (name "/SPI_SEL") (class "Default")
      (node (ref "J11") (pin "4") (pinfunction "4_4") (pintype "passive"))
      (node (ref "J16") (pin "4") (pinfunction "4_4") (pintype "passive"))
      (node (ref "J3") (pin "12") (pinfunction "12_12") (pintype "passive"))
    )
    (net (code "77") (name "/SPI_SEL2") (class "Default")
      (node (ref "J3") (pin "13") (pinfunction "13_13") (pintype "passive"))
      (node (ref "J4") (pin "4") (pinfunction "4_4") (pintype "passive"))
    )
    (net (code "78") (name "/TMR2") (class "Default")
      (node (ref "J16") (pin "1") (pinfunction "1_1") (pintype "passive"))
      (node (ref "J3") (pin "7") (pinfunction "7_7") (pintype "passive"))
    )
    (net (code "79") (name "/TMR3") (class "Default")
      (node (ref "J16") (pin "2") (pinfunction "2_2") (pintype "passive"))
      (node (ref "J3") (pin "8") (pinfunction "8_8") (pintype "passive"))
    )
    (net (code "80") (name "/TX0") (class "Default")
      (node (ref "J14") (pin "3") (pinfunction "3_3") (pintype "passive"))
      (node (ref "J3") (pin "3") (pinfunction "3_3") (pintype "passive"))
    )
    (net (code "81") (name "/TX1") (class "Default")
      (node (ref "J12") (pin "3") (pinfunction "3_3") (pintype "passive"))
      (node (ref "J3") (pin "5") (pinfunction "5_5") (pintype "passive"))
    )
    (net (code "82") (name "/~{RST}") (class "Default")
      (node (ref "J7") (pin "1") (pinfunction "1_1") (pintype "passive"))
      (node (ref "R2") (pin "1") (pinfunction "1_1") (pintype "passive"))
      (node (ref "R3") (pin "2") (pinfunction "2_2") (pintype "passive"))
      (node (ref "R4") (pin "1") (pinfunction "1_1") (pintype "passive"))
    )
    (net (code "83") (name "3.3V") (class "Default")
      (node (ref "C1") (pin "A") (pinfunction "+_A") (pintype "passive"))
      (node (ref "J15") (pin "1") (pinfunction "1_1") (pintype "passive"))
      (node (ref "J15") (pin "3") (pinfunction "3_3") (pintype "passive"))
      (node (ref "J3") (pin "1") (pinfunction "1_1") (pintype "passive"))
      (node (ref "U1") (pin "3") (pinfunction "OUT_3") (pintype "bidirectional"))
      (node (ref "U9") (pin "2") (pinfunction "VR1_2") (pintype "bidirectional"))
    )
    (net (code "84") (name "GND") (class "Default")
      (node (ref "C1") (pin "C") (pinfunction "-_C") (pintype "passive"))
      (node (ref "C10") (pin "1") (pinfunction "1_1") (pintype "passive"))
      (node (ref "C11") (pin "1") (pinfunction "1_1") (pintype "passive"))
      (node (ref "C12") (pin "2") (pinfunction "2_2") (pintype "passive"))
      (node (ref "C13") (pin "2") (pinfunction "2_2") (pintype "passive"))
      (node (ref "C14") (pin "2") (pinfunction "2_2") (pintype "passive"))
      (node (ref "C15") (pin "-") (pinfunction "-_-") (pintype "passive"))
      (node (ref "C16") (pin "2") (pinfunction "2_2") (pintype "passive"))
      (node (ref "C17") (pin "-") (pinfunction "-_-") (pintype "passive"))
      (node (ref "C18") (pin "2") (pinfunction "2_2") (pintype "passive"))
      (node (ref "C19") (pin "1") (pinfunction "1_1") (pintype "passive"))
      (node (ref "C2") (pin "2") (pinfunction "-_2") (pintype "passive"))
      (node (ref "C23") (pin "2") (pinfunction "2_2") (pintype "passive"))
      (node (ref "C24") (pin "2") (pinfunction "-_2") (pintype "passive"))
      (node (ref "C25") (pin "2") (pinfunction "2_2") (pintype "passive"))
      (node (ref "C27") (pin "1") (pinfunction "1_1") (pintype "passive"))
      (node (ref "C3") (pin "1") (pinfunction "1_1") (pintype "passive"))
      (node (ref "C4") (pin "-") (pinfunction "-_-") (pintype "passive"))
      (node (ref "C5") (pin "-") (pinfunction "-_-") (pintype "passive"))
      (node (ref "C6") (pin "-") (pinfunction "-_-") (pintype "passive"))
      (node (ref "C7") (pin "2") (pinfunction "2_2") (pintype "passive"))
      (node (ref "C8") (pin "-") (pinfunction "-_-") (pintype "passive"))
      (node (ref "C9") (pin "2") (pinfunction "2_2") (pintype "passive"))
      (node (ref "D1") (pin "A") (pinfunction "A_A") (pintype "passive"))
      (node (ref "J11") (pin "5") (pinfunction "5_5") (pintype "passive"))
      (node (ref "J12") (pin "2") (pinfunction "2_2") (pintype "passive"))
      (node (ref "J13") (pin "3") (pinfunction "3_3") (pintype "passive"))
      (node (ref "J14") (pin "2") (pinfunction "2_2") (pintype "passive"))
      (node (ref "J15") (pin "2") (pinfunction "2_2") (pintype "passive"))
      (node (ref "J15") (pin "4") (pinfunction "4_4") (pintype "passive"))
      (node (ref "J16") (pin "3") (pinfunction "3_3") (pintype "passive"))
      (node (ref "J20") (pin "1") (pinfunction "1_1") (pintype "passive"))
      (node (ref "J20") (pin "10") (pinfunction "10_10") (pintype "passive"))
      (node (ref "J20") (pin "13") (pinfunction "13_13") (pintype "passive"))
      (node (ref "J20") (pin "16") (pinfunction "16_16") (pintype "passive"))
      (node (ref "J20") (pin "19") (pinfunction "19_19") (pintype "passive"))
      (node (ref "J20") (pin "22") (pinfunction "22_22") (pintype "passive"))
      (node (ref "J20") (pin "25") (pinfunction "25_25") (pintype "passive"))
      (node (ref "J20") (pin "28") (pinfunction "28_28") (pintype "passive"))
      (node (ref "J20") (pin "31") (pinfunction "31_31") (pintype "passive"))
      (node (ref "J20") (pin "34") (pinfunction "34_34") (pintype "passive"))
      (node (ref "J20") (pin "37") (pinfunction "37_37") (pintype "passive"))
      (node (ref "J20") (pin "4") (pinfunction "4_4") (pintype "passive"))
      (node (ref "J20") (pin "40") (pinfunction "40_40") (pintype "passive"))
      (node (ref "J20") (pin "43") (pinfunction "43_43") (pintype "passive"))
      (node (ref "J20") (pin "46") (pinfunction "46_46") (pintype "passive"))
      (node (ref "J20") (pin "49") (pinfunction "49_49") (pintype "passive"))
      (node (ref "J20") (pin "7") (pinfunction "7_7") (pintype "passive"))
      (node (ref "J3") (pin "16") (pinfunction "16_16") (pintype "passive"))
      (node (ref "J3") (pin "2") (pinfunction "2_2") (pintype "passive"))
      (node (ref "J4") (pin "5") (pinfunction "5_5") (pintype "passive"))
      (node (ref "J5") (pin "2") (pinfunction "2_2") (pintype "passive"))
      (node (ref "J6") (pin "12") (pinfunction "12_12") (pintype "passive"))
      (node (ref "J6") (pin "15") (pinfunction "15_15") (pintype "passive"))
      (node (ref "J6") (pin "18") (pinfunction "18_18") (pintype "passive"))
      (node (ref "J6") (pin "21") (pinfunction "21_21") (pintype "passive"))
      (node (ref "J6") (pin "24") (pinfunction "24_24") (pintype "passive"))
      (node (ref "J6") (pin "27") (pinfunction "27_27") (pintype "passive"))
      (node (ref "J6") (pin "3") (pinfunction "3_3") (pintype "passive"))
      (node (ref "J6") (pin "30") (pinfunction "30_30") (pintype "passive"))
      (node (ref "J6") (pin "33") (pinfunction "33_33") (pintype "passive"))
      (node (ref "J6") (pin "36") (pinfunction "36_36") (pintype "passive"))
      (node (ref "J6") (pin "39") (pinfunction "39_39") (pintype "passive"))
      (node (ref "J6") (pin "42") (pinfunction "42_42") (pintype "passive"))
      (node (ref "J6") (pin "45") (pinfunction "45_45") (pintype "passive"))
      (node (ref "J6") (pin "48") (pinfunction "48_48") (pintype "passive"))
      (node (ref "J6") (pin "51") (pinfunction "51_51") (pintype "passive"))
      (node (ref "J6") (pin "6") (pinfunction "6_6") (pintype "passive"))
      (node (ref "J6") (pin "9") (pinfunction "9_9") (pintype "passive"))
      (node (ref "J7") (pin "3") (pinfunction "3_3") (pintype "passive"))
      (node (ref "J8") (pin "10") (pinfunction "10_10") (pintype "passive"))
      (node (ref "R23") (pin "1") (pinfunction "1_1") (pintype "passive"))
      (node (ref "U1") (pin "2") (pinfunction "GND_2") (pintype "bidirectional"))
      (node (ref "U11") (pin "1") (pinfunction "GND_1") (pintype "bidirectional"))
      (node (ref "U14") (pin "20") (pinfunction "AVSS_20") (pintype "power_in"))
      (node (ref "U14") (pin "25") (pinfunction "VSS_25") (pintype "power_in"))
      (node (ref "U14") (pin "41") (pinfunction "VSS_41") (pintype "power_in"))
      (node (ref "U14") (pin "56") (pinfunction "VSS_56") (pintype "power_in"))
      (node (ref "U14") (pin "9") (pinfunction "VSS_9") (pintype "power_in"))
      (node (ref "U15") (pin "10") (pinfunction "GND_10") (pintype "power_in"))
      (node (ref "U15") (pin "2") (pinfunction "RTRY_2") (pintype "input"))
      (node (ref "U15") (pin "8") (pinfunction "LSS_8") (pintype "output"))
      (node (ref "U15") (pin "PAD") (pinfunction "PAD_PAD") (pintype "output"))
      (node (ref "U2") (pin "3") (pinfunction "GND_3") (pintype "bidirectional"))
      (node (ref "U2") (pin "5") (pinfunction "SD_5") (pintype "bidirectional"))
      (node (ref "U2") (pin "6") (pinfunction "GND_6") (pintype "bidirectional"))
      (node (ref "U3") (pin "10") (pinfunction "GND_10") (pintype "power_in"))
      (node (ref "U3") (pin "2") (pinfunction "RTRY_2") (pintype "input"))
      (node (ref "U3") (pin "8") (pinfunction "LSS_8") (pintype "output"))
      (node (ref "U3") (pin "PAD") (pinfunction "PAD_PAD") (pintype "output"))
      (node (ref "U4") (pin "10") (pinfunction "GND_10") (pintype "power_in"))
      (node (ref "U4") (pin "2") (pinfunction "RTRY_2") (pintype "input"))
      (node (ref "U4") (pin "8") (pinfunction "LSS_8") (pintype "output"))
      (node (ref "U4") (pin "PAD") (pinfunction "PAD_PAD") (pintype "output"))
      (node (ref "U5") (pin "10") (pinfunction "GND_10") (pintype "power_in"))
      (node (ref "U5") (pin "2") (pinfunction "RTRY_2") (pintype "input"))
      (node (ref "U5") (pin "8") (pinfunction "LSS_8") (pintype "output"))
      (node (ref "U5") (pin "PAD") (pinfunction "PAD_PAD") (pintype "output"))
      (node (ref "U9") (pin "1") (pinfunction "GND_1") (pintype "bidirectional"))
    )
    (net (code "85") (name "Net-(C19-Pad2)") (class "Default")
      (node (ref "C19") (pin "2") (pinfunction "2_2") (pintype "passive"))
      (node (ref "R4") (pin "2") (pinfunction "2_2") (pintype "passive"))
    )
    (net (code "86") (name "Net-(D2-A)") (class "Default")
      (node (ref "D2") (pin "2") (pinfunction "A_2") (pintype "passive"))
      (node (ref "J5") (pin "1") (pinfunction "1_1") (pintype "passive"))
    )
    (net (code "87") (name "Net-(D4-A)") (class "Default")
      (node (ref "D4") (pin "2") (pinfunction "A_2") (pintype "passive"))
      (node (ref "J20") (pin "14") (pinfunction "14_14") (pintype "passive"))
    )
    (net (code "88") (name "Net-(D4-C)") (class "Default")
      (node (ref "D4") (pin "1") (pinfunction "C_1") (pintype "passive"))
      (node (ref "J20") (pin "11") (pinfunction "11_11") (pintype "passive"))
      (node (ref "J20") (pin "2") (pinfunction "2_2") (pintype "passive"))
      (node (ref "J20") (pin "5") (pinfunction "5_5") (pintype "passive"))
      (node (ref "J20") (pin "8") (pinfunction "8_8") (pintype "passive"))
    )
    (net (code "89") (name "Net-(D6-A)") (class "Default")
      (node (ref "D6") (pin "2") (pinfunction "A_2") (pintype "passive"))
      (node (ref "J6") (pin "14") (pinfunction "14_14") (pintype "passive"))
    )
    (net (code "90") (name "Net-(D6-C)") (class "Default")
      (node (ref "D6") (pin "1") (pinfunction "C_1") (pintype "passive"))
      (node (ref "J6") (pin "11") (pinfunction "11_11") (pintype "passive"))
      (node (ref "J6") (pin "2") (pinfunction "2_2") (pintype "passive"))
      (node (ref "J6") (pin "5") (pinfunction "5_5") (pintype "passive"))
      (node (ref "J6") (pin "8") (pinfunction "8_8") (pintype "passive"))
    )
    (net (code "91") (name "Net-(LED1-PadC)") (class "Default")
      (node (ref "LED1") (pin "C") (pinfunction "C_C") (pintype "passive"))
      (node (ref "R19") (pin "1") (pinfunction "1_1") (pintype "passive"))
    )
    (net (code "92") (name "Net-(U2-FB)") (class "Default")
      (node (ref "R22") (pin "1") (pinfunction "1_1") (pintype "passive"))
      (node (ref "R23") (pin "2") (pinfunction "2_2") (pintype "passive"))
      (node (ref "U2") (pin "4") (pinfunction "FB_4") (pintype "bidirectional"))
    )
    (net (code "93") (name "Net-(U2-OUT)") (class "Default")
      (node (ref "D1") (pin "C") (pinfunction "C_C") (pintype "passive"))
      (node (ref "L1") (pin "1") (pinfunction "1_1") (pintype "passive"))
      (node (ref "U2") (pin "2") (pinfunction "OUT_2") (pintype "bidirectional"))
    )
    (net (code "94") (name "Net-(U3-OUT1)") (class "Default")
      (node (ref "J2") (pin "3") (pinfunction "3_3") (pintype "passive"))
      (node (ref "U3") (pin "7") (pinfunction "OUT1_7") (pintype "output"))
    )
    (net (code "95") (name "Net-(U3-OUT2)") (class "Default")
      (node (ref "J2") (pin "4") (pinfunction "4_4") (pintype "passive"))
      (node (ref "U3") (pin "9") (pinfunction "OUT2_9") (pintype "input"))
    )
    (net (code "96") (name "Net-(U4-OUT1)") (class "Default")
      (node (ref "J1") (pin "2") (pinfunction "2_2") (pintype "passive"))
      (node (ref "U4") (pin "7") (pinfunction "OUT1_7") (pintype "output"))
    )
    (net (code "97") (name "Net-(U4-OUT2)") (class "Default")
      (node (ref "J1") (pin "1") (pinfunction "1_1") (pintype "passive"))
      (node (ref "U4") (pin "9") (pinfunction "OUT2_9") (pintype "input"))
    )
    (net (code "98") (name "Net-(U5-OUT1)") (class "Default")
      (node (ref "J1") (pin "4") (pinfunction "4_4") (pintype "passive"))
      (node (ref "U5") (pin "7") (pinfunction "OUT1_7") (pintype "output"))
    )
    (net (code "99") (name "Net-(U5-OUT2)") (class "Default")
      (node (ref "J1") (pin "3") (pinfunction "3_3") (pintype "passive"))
      (node (ref "U5") (pin "9") (pinfunction "OUT2_9") (pintype "input"))
    )
    (net (code "100") (name "Net-(U9-EN)") (class "Default")
      (node (ref "C27") (pin "2") (pinfunction "2_2") (pintype "passive"))
      (node (ref "R32") (pin "1") (pinfunction "1_1") (pintype "passive"))
      (node (ref "U9") (pin "7") (pinfunction "VR2_7") (pintype "bidirectional"))
      (node (ref "U9") (pin "8") (pinfunction "EN_8") (pintype "input"))
    )
    (net (code "101") (name "Net-(U14-AVDD)") (class "Default")
      (node (ref "C9") (pin "1") (pinfunction "1_1") (pintype "passive"))
      (node (ref "R1") (pin "2") (pinfunction "2_2") (pintype "passive"))
      (node (ref "U14") (pin "19") (pinfunction "AVDD_19") (pintype "power_in"))
    )
    (net (code "102") (name "Net-(U14-VDDCORE{slash}VCAP)") (class "Default")
      (node (ref "C3") (pin "2") (pinfunction "2_2") (pintype "passive"))
      (node (ref "U14") (pin "10") (pinfunction "VDDCORE/VCAP_10") (pintype "power_in"))
    )
    (net (code "103") (name "Net-(U14-~{MCLR{slash}}RG5)") (class "Default")
      (node (ref "R3") (pin "1") (pinfunction "1_1") (pintype "passive"))
      (node (ref "U14") (pin "7") (pinfunction "~{MCLR/}RG5_7") (pintype "input"))
    )
    (net (code "104") (name "Net-(U15-OUT1)") (class "Default")
      (node (ref "J2") (pin "1") (pinfunction "1_1") (pintype "passive"))
      (node (ref "U15") (pin "7") (pinfunction "OUT1_7") (pintype "output"))
    )
    (net (code "105") (name "Net-(U15-OUT2)") (class "Default")
      (node (ref "J2") (pin "2") (pinfunction "2_2") (pintype "passive"))
      (node (ref "U15") (pin "9") (pinfunction "OUT2_9") (pintype "input"))
    )
    (net (code "106") (name "unconnected-(J12-Pad1)") (class "Default")
      (node (ref "J12") (pin "1") (pinfunction "1_1") (pintype "passive"))
    )
    (net (code "107") (name "unconnected-(J14-Pad1)") (class "Default")
      (node (ref "J14") (pin "1") (pinfunction "1_1") (pintype "passive"))
    )
    (net (code "108") (name "unconnected-(U$1-1-PadP$2)") (class "Default")
      (node (ref "U$1") (pin "P$2") (pinfunction "1_P$2") (pintype "bidirectional"))
    )
    (net (code "109") (name "unconnected-(U$2-1-PadP$2)") (class "Default")
      (node (ref "U$2") (pin "P$2") (pinfunction "1_P$2") (pintype "bidirectional"))
    )
    (net (code "110") (name "unconnected-(U$7-1-PadP$2)") (class "Default")
      (node (ref "U$7") (pin "P$2") (pinfunction "1_P$2") (pintype "bidirectional"))
    )
    (net (code "111") (name "unconnected-(U$8-1-PadP$2)") (class "Default")
      (node (ref "U$8") (pin "P$2") (pinfunction "1_P$2") (pintype "bidirectional"))
    )
    (net (code "112") (name "unconnected-(U3-FAULT-Pad1)") (class "Default")
      (node (ref "U3") (pin "1") (pinfunction "FAULT_1") (pintype "output"))
    )
    (net (code "113") (name "unconnected-(U4-FAULT-Pad1)") (class "Default")
      (node (ref "U4") (pin "1") (pinfunction "FAULT_1") (pintype "output"))
    )
    (net (code "114") (name "unconnected-(U5-FAULT-Pad1)") (class "Default")
      (node (ref "U5") (pin "1") (pinfunction "FAULT_1") (pintype "output"))
    )
    (net (code "115") (name "unconnected-(U14-RE0{slash}~{RD{slash}}P2D-Pad2)") (class "Default")
      (node (ref "U14") (pin "2") (pinfunction "RE0/~{RD/}P2D_2") (pintype "bidirectional"))
    )
    (net (code "116") (name "unconnected-(U14-RE1{slash}~{WR{slash}}P2C-Pad1)") (class "Default")
      (node (ref "U14") (pin "1") (pinfunction "RE1/~{WR/}P2C_1") (pintype "bidirectional"))
    )
    (net (code "117") (name "unconnected-(U14-RG0{slash}ECCP3{slash}P3A-Pad3)") (class "Default")
      (node (ref "U14") (pin "3") (pinfunction "RG0/ECCP3/P3A_3") (pintype "bidirectional"))
    )
    (net (code "118") (name "unconnected-(U15-FAULT-Pad1)") (class "Default")
      (node (ref "U15") (pin "1") (pinfunction "FAULT_1") (pintype "output"))
    )
  )
)
